# Esp32_Wroom_Contr_le_de_DELs.net
KiCad netlist of a schematic drawn in Altium Designer
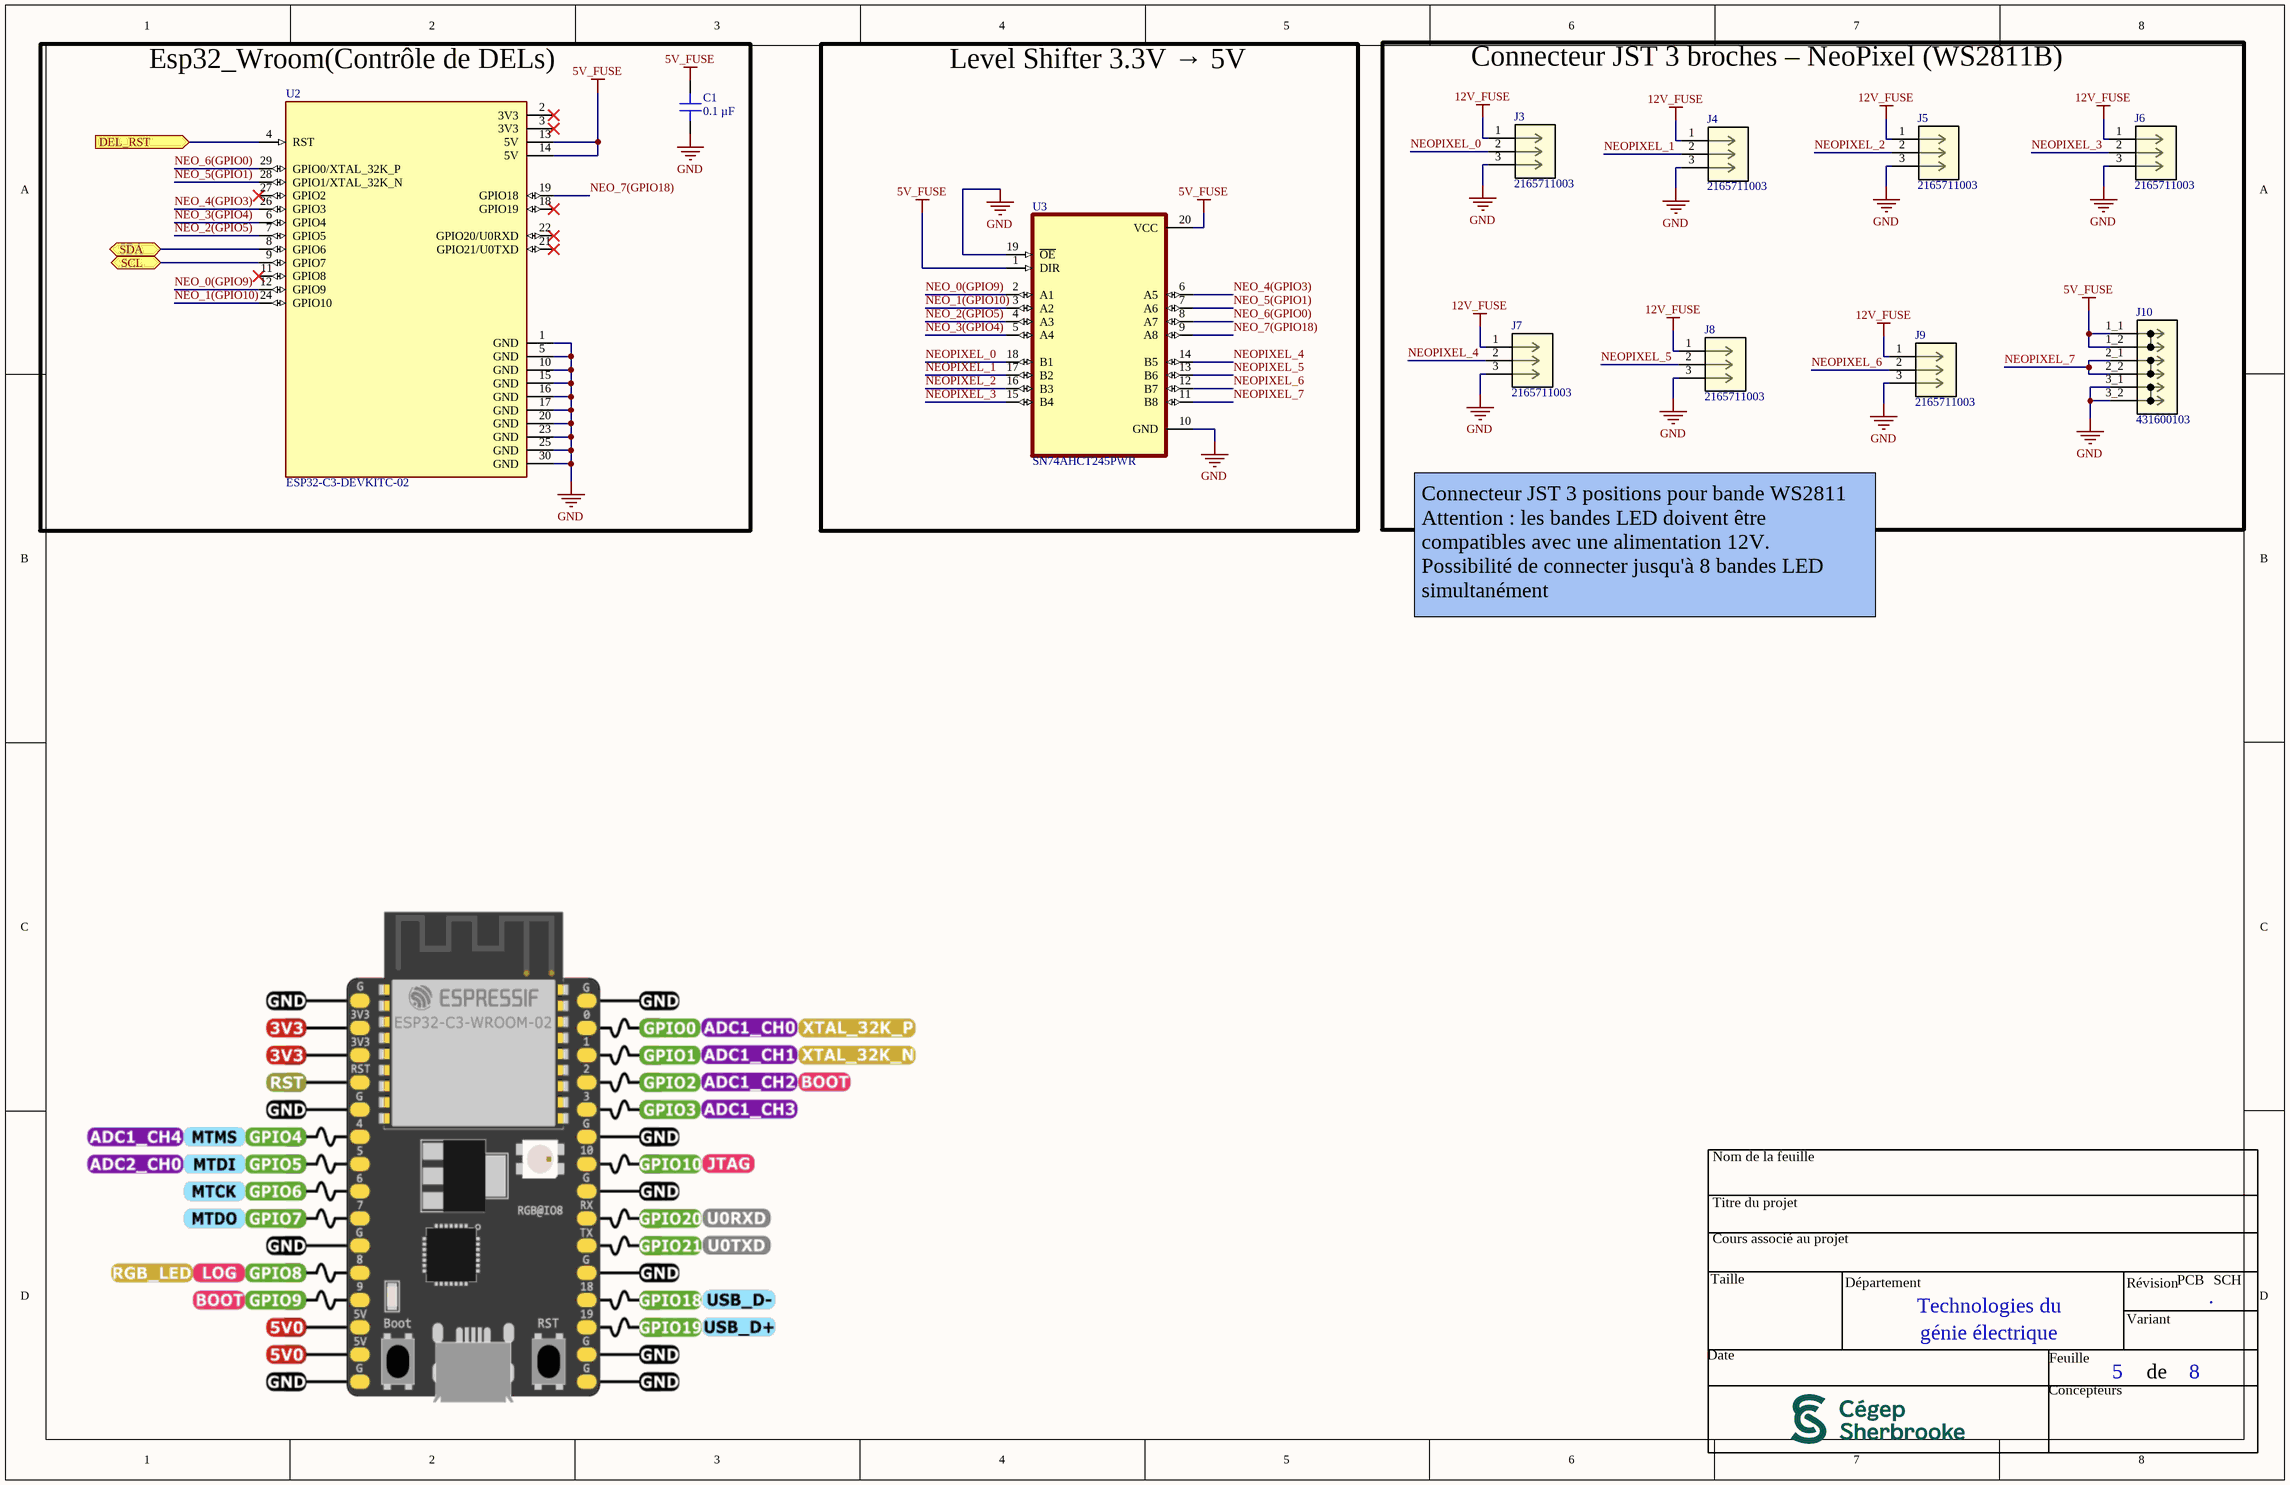
[diagram p0: Esp32_Wroom(Contrôle de DELs).SchDoc]

(export (version "E")
  (design (tool "Eeschema 10.0.6"))
  (components
    (comp (ref "C1")
      (value "0.1 µF")
      (footprint "CAP 0805_2012")
      (description "CAP CER 0.1UF 16V X7R 0805")
      (fields
        (field (name "PART NUMBER") "C0805C104M4RAC7800")
        (field (name "CAPACITANCE") "0.1 µF")
        (field (name "MANUFACTURER") "KEMET")
      )
      (libsource (lib "Celestial Altium Library - altium_library") (part "Capacitor"))
    )
    (comp (ref "J3")
      (value "2165711003")
      (footprint "CONN_2165710003-SD_03_MOL")
      (fields (field (name "COPYRIGHT") "Copyright (C) 2026 Ultra Librarian. All rights reserved."))
      (libsource (lib "2165711003") (part "2165711003"))
    )
    (comp (ref "J4")
      (value "2165711003")
      (footprint "CONN_2165710003-SD_03_MOL")
      (fields (field (name "COPYRIGHT") "Copyright (C) 2026 Ultra Librarian. All rights reserved."))
      (libsource (lib "2165711003") (part "2165711003"))
    )
    (comp (ref "J5")
      (value "2165711003")
      (footprint "CONN_2165710003-SD_03_MOL")
      (fields (field (name "COPYRIGHT") "Copyright (C) 2026 Ultra Librarian. All rights reserved."))
      (libsource (lib "2165711003") (part "2165711003"))
    )
    (comp (ref "J6")
      (value "2165711003")
      (footprint "CONN_2165710003-SD_03_MOL")
      (fields (field (name "COPYRIGHT") "Copyright (C) 2026 Ultra Librarian. All rights reserved."))
      (libsource (lib "2165711003") (part "2165711003"))
    )
    (comp (ref "J7")
      (value "2165711003")
      (footprint "CONN_2165710003-SD_03_MOL")
      (fields (field (name "COPYRIGHT") "Copyright (C) 2026 Ultra Librarian. All rights reserved."))
      (libsource (lib "2165711003") (part "2165711003"))
    )
    (comp (ref "J8")
      (value "2165711003")
      (footprint "CONN_2165710003-SD_03_MOL")
      (fields (field (name "COPYRIGHT") "Copyright (C) 2026 Ultra Librarian. All rights reserved."))
      (libsource (lib "2165711003") (part "2165711003"))
    )
    (comp (ref "J9")
      (value "2165711003")
      (footprint "CONN_2165710003-SD_03_MOL")
      (fields (field (name "COPYRIGHT") "Copyright (C) 2026 Ultra Librarian. All rights reserved."))
      (libsource (lib "2165711003") (part "2165711003"))
    )
    (comp (ref "J10")
      (value "431600103")
      (footprint "CONN_431600001-SD_V_03_MOL")
      (description "Sabre Vertical Header, 3 Circuits, Glow-Wire Capable, PCB Thickness 1.60mm, without Board Lock")
      (fields (field (name "COPYRIGHT") "Copyright (C) 2026 Ultra Librarian. All rights reserved."))
      (libsource (lib "431600103") (part "431600103"))
    )
    (comp (ref "U2")
      (value "ESP32-C3-DEVKITC-02")
      (footprint "XCVR_ESP32-C3-DEVKITC-02")
      (fields (field (name "MF") "Espressif Systems") (field (name "MP") "ESP32-C3-DevKitC-02"))
      (libsource (lib "ESP32-C3-DEVKITC-02") (part "ESP32-C3-DEVKITC-02"))
    )
    (comp (ref "U3")
      (value "SN74AHCT245PWR")
      (footprint "SOP65P640X120-20N")
      (libsource (lib "SN74AHCT245PWR") (part "SN74AHCT245PWR"))
    )
  )
  (nets
    (net (code "2") (name "/DEL_RST") (class "Default")
      (node (ref "U2") (pin "4") (pinfunction "RST_4") (pintype "input"))
    )
    (net (code "3") (name "/NEOPIXEL_0") (class "Default")
      (node (ref "J3") (pin "2") (pinfunction "2_2") (pintype "passive"))
      (node (ref "U3") (pin "18") (pinfunction "B1_18") (pintype "bidirectional"))
    )
    (net (code "4") (name "/NEOPIXEL_1") (class "Default")
      (node (ref "J4") (pin "2") (pinfunction "2_2") (pintype "passive"))
      (node (ref "U3") (pin "17") (pinfunction "B2_17") (pintype "bidirectional"))
    )
    (net (code "5") (name "/NEOPIXEL_2") (class "Default")
      (node (ref "J5") (pin "2") (pinfunction "2_2") (pintype "passive"))
      (node (ref "U3") (pin "16") (pinfunction "B3_16") (pintype "bidirectional"))
    )
    (net (code "6") (name "/NEOPIXEL_3") (class "Default")
      (node (ref "J6") (pin "2") (pinfunction "2_2") (pintype "passive"))
      (node (ref "U3") (pin "15") (pinfunction "B4_15") (pintype "bidirectional"))
    )
    (net (code "7") (name "/NEOPIXEL_4") (class "Default")
      (node (ref "J7") (pin "2") (pinfunction "2_2") (pintype "passive"))
      (node (ref "U3") (pin "14") (pinfunction "B5_14") (pintype "bidirectional"))
    )
    (net (code "8") (name "/NEOPIXEL_5") (class "Default")
      (node (ref "J8") (pin "2") (pinfunction "2_2") (pintype "passive"))
      (node (ref "U3") (pin "13") (pinfunction "B6_13") (pintype "bidirectional"))
    )
    (net (code "9") (name "/NEOPIXEL_6") (class "Default")
      (node (ref "J9") (pin "2") (pinfunction "2_2") (pintype "passive"))
      (node (ref "U3") (pin "12") (pinfunction "B7_12") (pintype "bidirectional"))
    )
    (net (code "10") (name "/NEOPIXEL_7") (class "Default")
      (node (ref "J10") (pin "2_1") (pinfunction "2_1_2_1") (pintype "passive"))
      (node (ref "J10") (pin "2_2") (pinfunction "2_2_2_2") (pintype "passive"))
      (node (ref "U3") (pin "11") (pinfunction "B8_11") (pintype "bidirectional"))
    )
    (net (code "11") (name "/NEO_0(GPIO9)") (class "Default")
      (node (ref "U2") (pin "12") (pinfunction "GPIO9_12") (pintype "bidirectional"))
      (node (ref "U3") (pin "2") (pinfunction "A1_2") (pintype "bidirectional"))
    )
    (net (code "12") (name "/NEO_1(GPIO10)") (class "Default")
      (node (ref "U2") (pin "24") (pinfunction "GPIO10_24") (pintype "bidirectional"))
      (node (ref "U3") (pin "3") (pinfunction "A2_3") (pintype "bidirectional"))
    )
    (net (code "13") (name "/NEO_2(GPIO5)") (class "Default")
      (node (ref "U2") (pin "7") (pinfunction "GPIO5_7") (pintype "bidirectional"))
      (node (ref "U3") (pin "4") (pinfunction "A3_4") (pintype "bidirectional"))
    )
    (net (code "14") (name "/NEO_3(GPIO4)") (class "Default")
      (node (ref "U2") (pin "6") (pinfunction "GPIO4_6") (pintype "bidirectional"))
      (node (ref "U3") (pin "5") (pinfunction "A4_5") (pintype "bidirectional"))
    )
    (net (code "15") (name "/NEO_4(GPIO3)") (class "Default")
      (node (ref "U2") (pin "26") (pinfunction "GPIO3_26") (pintype "bidirectional"))
      (node (ref "U3") (pin "6") (pinfunction "A5_6") (pintype "bidirectional"))
    )
    (net (code "16") (name "/NEO_5(GPIO1)") (class "Default")
      (node (ref "U2") (pin "28") (pinfunction "GPIO1/XTAL_32K_N_28") (pintype "bidirectional"))
      (node (ref "U3") (pin "7") (pinfunction "A6_7") (pintype "bidirectional"))
    )
    (net (code "17") (name "/NEO_6(GPIO0)") (class "Default")
      (node (ref "U2") (pin "29") (pinfunction "GPIO0/XTAL_32K_P_29") (pintype "bidirectional"))
      (node (ref "U3") (pin "8") (pinfunction "A7_8") (pintype "bidirectional"))
    )
    (net (code "18") (name "/NEO_7(GPIO18)") (class "Default")
      (node (ref "U2") (pin "19") (pinfunction "GPIO18_19") (pintype "bidirectional"))
      (node (ref "U3") (pin "9") (pinfunction "A8_9") (pintype "bidirectional"))
    )
    (net (code "19") (name "/SCL") (class "Default")
      (node (ref "U2") (pin "9") (pinfunction "GPIO7_9") (pintype "bidirectional"))
    )
    (net (code "20") (name "/SDA") (class "Default")
      (node (ref "U2") (pin "8") (pinfunction "GPIO6_8") (pintype "bidirectional"))
    )
    (net (code "21") (name "5V_FUSE") (class "Default")
      (node (ref "C1") (pin "2") (pinfunction "2_2") (pintype "passive"))
      (node (ref "J10") (pin "1_1") (pinfunction "1_1_1_1") (pintype "passive"))
      (node (ref "J10") (pin "1_2") (pinfunction "1_2_1_2") (pintype "passive"))
      (node (ref "U2") (pin "13") (pinfunction "5V_13") (pintype "power_in"))
      (node (ref "U2") (pin "14") (pinfunction "5V_14") (pintype "power_in"))
      (node (ref "U3") (pin "1") (pinfunction "DIR_1") (pintype "input"))
      (node (ref "U3") (pin "20") (pinfunction "VCC_20") (pintype "power_in"))
    )
    (net (code "22") (name "12V_FUSE") (class "Default")
      (node (ref "J3") (pin "1") (pinfunction "1_1") (pintype "passive"))
      (node (ref "J4") (pin "1") (pinfunction "1_1") (pintype "passive"))
      (node (ref "J5") (pin "1") (pinfunction "1_1") (pintype "passive"))
      (node (ref "J6") (pin "1") (pinfunction "1_1") (pintype "passive"))
      (node (ref "J7") (pin "1") (pinfunction "1_1") (pintype "passive"))
      (node (ref "J8") (pin "1") (pinfunction "1_1") (pintype "passive"))
      (node (ref "J9") (pin "1") (pinfunction "1_1") (pintype "passive"))
    )
    (net (code "23") (name "GND") (class "Default")
      (node (ref "C1") (pin "1") (pinfunction "1_1") (pintype "passive"))
      (node (ref "J10") (pin "3_1") (pinfunction "3_1_3_1") (pintype "passive"))
      (node (ref "J10") (pin "3_2") (pinfunction "3_2_3_2") (pintype "passive"))
      (node (ref "J3") (pin "3") (pinfunction "3_3") (pintype "passive"))
      (node (ref "J4") (pin "3") (pinfunction "3_3") (pintype "passive"))
      (node (ref "J5") (pin "3") (pinfunction "3_3") (pintype "passive"))
      (node (ref "J6") (pin "3") (pinfunction "3_3") (pintype "passive"))
      (node (ref "J7") (pin "3") (pinfunction "3_3") (pintype "passive"))
      (node (ref "J8") (pin "3") (pinfunction "3_3") (pintype "passive"))
      (node (ref "J9") (pin "3") (pinfunction "3_3") (pintype "passive"))
      (node (ref "U2") (pin "1") (pinfunction "GND_1") (pintype "power_in"))
      (node (ref "U2") (pin "10") (pinfunction "GND_10") (pintype "power_in"))
      (node (ref "U2") (pin "15") (pinfunction "GND_15") (pintype "power_in"))
      (node (ref "U2") (pin "16") (pinfunction "GND_16") (pintype "power_in"))
      (node (ref "U2") (pin "17") (pinfunction "GND_17") (pintype "power_in"))
      (node (ref "U2") (pin "20") (pinfunction "GND_20") (pintype "power_in"))
      (node (ref "U2") (pin "23") (pinfunction "GND_23") (pintype "power_in"))
      (node (ref "U2") (pin "25") (pinfunction "GND_25") (pintype "power_in"))
      (node (ref "U2") (pin "30") (pinfunction "GND_30") (pintype "power_in"))
      (node (ref "U2") (pin "5") (pinfunction "GND_5") (pintype "power_in"))
      (node (ref "U3") (pin "10") (pinfunction "GND_10") (pintype "power_in"))
      (node (ref "U3") (pin "19") (pinfunction "~{OE}_19") (pintype "input"))
    )
    (net (code "24") (name "unconnected-(U2-3V3-Pad2)") (class "Default")
      (node (ref "U2") (pin "2") (pinfunction "3V3_2") (pintype "power_in+no_connect"))
    )
    (net (code "25") (name "unconnected-(U2-3V3-Pad3)") (class "Default")
      (node (ref "U2") (pin "3") (pinfunction "3V3_3") (pintype "power_in+no_connect"))
    )
    (net (code "26") (name "unconnected-(U2-GPIO2-Pad27)") (class "Default")
      (node (ref "U2") (pin "27") (pinfunction "GPIO2_27") (pintype "bidirectional+no_connect"))
    )
    (net (code "27") (name "unconnected-(U2-GPIO8-Pad11)") (class "Default")
      (node (ref "U2") (pin "11") (pinfunction "GPIO8_11") (pintype "bidirectional+no_connect"))
    )
    (net (code "28") (name "unconnected-(U2-GPIO19-Pad18)") (class "Default")
      (node (ref "U2") (pin "18") (pinfunction "GPIO19_18") (pintype "bidirectional+no_connect"))
    )
    (net (code "29") (name "unconnected-(U2-GPIO20{slash}U0RXD-Pad22)") (class "Default")
      (node (ref "U2") (pin "22") (pinfunction "GPIO20/U0RXD_22") (pintype "bidirectional+no_connect"))
    )
    (net (code "30") (name "unconnected-(U2-GPIO21{slash}U0TXD-Pad21)") (class "Default")
      (node (ref "U2") (pin "21") (pinfunction "GPIO21/U0TXD_21") (pintype "bidirectional+no_connect"))
    )
  )
)
